# tiva_shield.net
KiCad netlist of a schematic drawn in Altium Designer
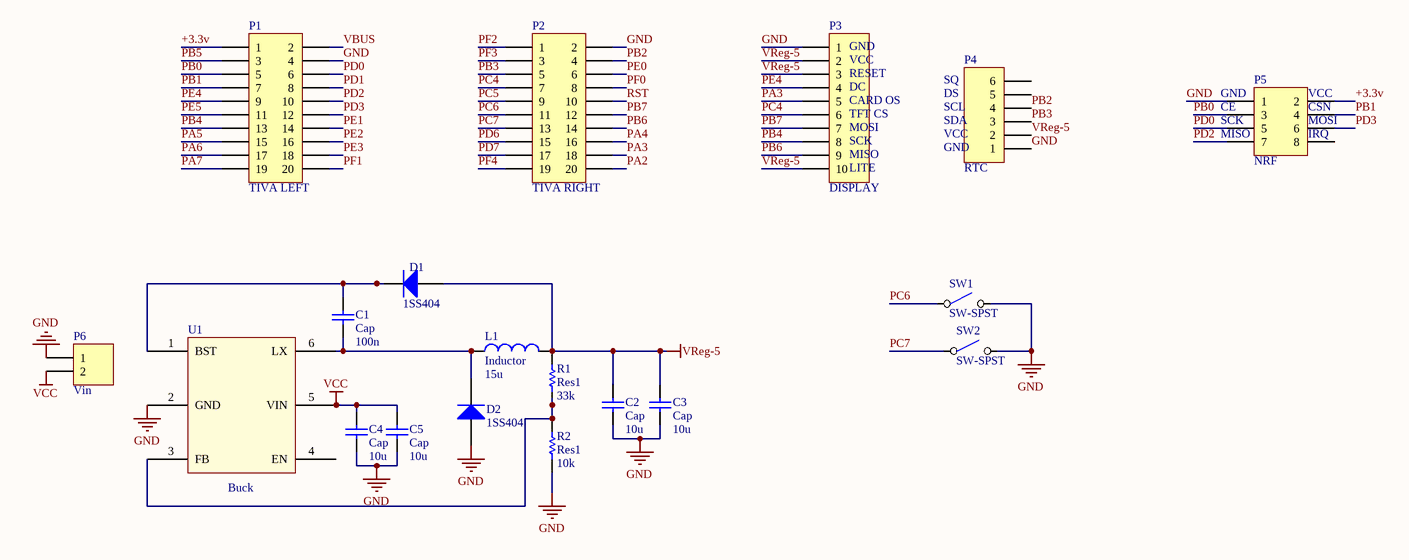
[diagram p0: tiva_shield.SchDoc]

(export (version "E")
  (design (tool "Eeschema 10.0.6"))
  (components
    (comp (ref "C1")
      (value "Cap")
      (footprint "0603E")
      (description "Capacitor")
      (fields (field (name "ALTIUM_VALUE") "100n") (field (name "PUBLISHER") "Altium Limited"))
      (libsource (lib "Miscellaneous Devices") (part "Cap"))
    )
    (comp (ref "C2")
      (value "Cap")
      (footprint "C0805")
      (description "Capacitor")
      (fields (field (name "ALTIUM_VALUE") "10u") (field (name "PUBLISHER") "Altium Limited"))
      (libsource (lib "Miscellaneous Devices") (part "Cap"))
    )
    (comp (ref "C3")
      (value "Cap")
      (footprint "C0805")
      (description "Capacitor")
      (fields (field (name "ALTIUM_VALUE") "10u") (field (name "PUBLISHER") "Altium Limited"))
      (libsource (lib "Miscellaneous Devices") (part "Cap"))
    )
    (comp (ref "C4")
      (value "Cap")
      (footprint "C0805")
      (description "Capacitor")
      (fields (field (name "ALTIUM_VALUE") "10u") (field (name "PUBLISHER") "Altium Limited"))
      (libsource (lib "Miscellaneous Devices") (part "Cap"))
    )
    (comp (ref "C5")
      (value "Cap")
      (footprint "C0805")
      (description "Capacitor")
      (fields (field (name "ALTIUM_VALUE") "10u") (field (name "PUBLISHER") "Altium Limited"))
      (libsource (lib "Miscellaneous Devices") (part "Cap"))
    )
    (comp (ref "D1")
      (value "1SS404")
      (footprint "SOD-323")
      (description "Silicon RF Switching Diode for VHF Band Switching in TV/VTR Tuners")
      (fields (field (name "PUBLISHER") "Altium Limited"))
      (libsource (lib "Infineon Discrete Diode") (part "BA592"))
    )
    (comp (ref "D2")
      (value "1SS404")
      (footprint "SOD-323")
      (description "Silicon RF Switching Diode for VHF Band Switching in TV/VTR Tuners")
      (fields (field (name "PUBLISHER") "Altium Limited"))
      (libsource (lib "Infineon Discrete Diode") (part "BA592"))
    )
    (comp (ref "L1")
      (value "Inductor")
      (footprint "5828-INDUCTOR")
      (fields (field (name "ALTIUM_VALUE") "15u") (field (name "PUBLISHER") "Altium Limited"))
      (libsource (lib "Miscellaneous Devices") (part "Inductor"))
    )
    (comp (ref "P1")
      (value "TIVA LEFT")
      (footprint "HDR2X10")
      (description "Header, 10-Pin, Dual row")
      (fields (field (name "PUBLISHER") "Altium Limited"))
      (libsource (lib "Miscellaneous Connectors") (part "Header 10X2"))
    )
    (comp (ref "P2")
      (value "TIVA RIGHT")
      (footprint "HDR2X10")
      (description "Header, 10-Pin, Dual row")
      (fields (field (name "PUBLISHER") "Altium Limited"))
      (libsource (lib "Miscellaneous Connectors") (part "Header 10X2"))
    )
    (comp (ref "P3")
      (value "DISPLAY")
      (footprint "HDR1X10")
      (description "Header, 10-Pin")
      (fields (field (name "PUBLISHER") "Altium Limited"))
      (libsource (lib "Miscellaneous Connectors") (part "Header 10"))
    )
    (comp (ref "P4")
      (value "RTC")
      (footprint "HDR1X6")
      (description "Header, 6-Pin")
      (fields (field (name "PUBLISHER") "Altium Limited"))
      (libsource (lib "Miscellaneous Connectors") (part "Header 6"))
    )
    (comp (ref "P5")
      (value "NRF")
      (footprint "HDR2X4")
      (description "Header, 4-Pin, Dual row")
      (fields (field (name "PUBLISHER") "Altium Limited"))
      (libsource (lib "Miscellaneous Connectors") (part "Header 4X2"))
    )
    (comp (ref "P6")
      (value "Vin")
      (footprint "HDR1X2")
      (description "Header, 2-Pin")
      (fields (field (name "PUBLISHER") "Altium Limited"))
      (libsource (lib "Miscellaneous Connectors") (part "Header 2"))
    )
    (comp (ref "R1")
      (value "Res1")
      (footprint "0603E")
      (description "Resistor")
      (fields (field (name "ALTIUM_VALUE") "33k") (field (name "PUBLISHER") "Altium Limited"))
      (libsource (lib "Miscellaneous Devices") (part "Res1"))
    )
    (comp (ref "R2")
      (value "Res1")
      (footprint "0603E")
      (description "Resistor")
      (fields (field (name "ALTIUM_VALUE") "10k") (field (name "PUBLISHER") "Altium Limited"))
      (libsource (lib "Miscellaneous Devices") (part "Res1"))
    )
    (comp (ref "SW1")
      (value "SW-SPST")
      (footprint "Switch - SMD")
      (libsource (lib "KBsch01") (part "SW-SPST"))
    )
    (comp (ref "SW2")
      (value "SW-SPST")
      (footprint "Switch - SMD")
      (libsource (lib "KBsch01") (part "SW-SPST"))
    )
    (comp (ref "U1") (value "Buck") (footprint "SOT23-6") (libsource (lib "aoz1280ci") (part "Component_1")))
  )
  (nets
    (net (code "1") (name "/+3.3v") (class "Default")
      (node (ref "P1") (pin "1") (pinfunction "1_1") (pintype "passive"))
      (node (ref "P5") (pin "2") (pinfunction "2_2") (pintype "passive"))
    )
    (net (code "2") (name "/PA2") (class "Default")
      (node (ref "P2") (pin "20") (pinfunction "20_20") (pintype "passive"))
    )
    (net (code "3") (name "/PA3") (class "Default")
      (node (ref "P2") (pin "18") (pinfunction "18_18") (pintype "passive"))
      (node (ref "P3") (pin "5") (pinfunction "5_5") (pintype "passive"))
    )
    (net (code "4") (name "/PA4") (class "Default")
      (node (ref "P2") (pin "16") (pinfunction "16_16") (pintype "passive"))
    )
    (net (code "5") (name "/PA5") (class "Default")
      (node (ref "P1") (pin "15") (pinfunction "15_15") (pintype "passive"))
    )
    (net (code "6") (name "/PA6") (class "Default")
      (node (ref "P1") (pin "17") (pinfunction "17_17") (pintype "passive"))
    )
    (net (code "7") (name "/PA7") (class "Default")
      (node (ref "P1") (pin "19") (pinfunction "19_19") (pintype "passive"))
    )
    (net (code "8") (name "/PB0") (class "Default")
      (node (ref "P1") (pin "5") (pinfunction "5_5") (pintype "passive"))
      (node (ref "P5") (pin "3") (pinfunction "3_3") (pintype "passive"))
    )
    (net (code "9") (name "/PB1") (class "Default")
      (node (ref "P1") (pin "7") (pinfunction "7_7") (pintype "passive"))
      (node (ref "P5") (pin "4") (pinfunction "4_4") (pintype "passive"))
    )
    (net (code "10") (name "/PB2") (class "Default")
      (node (ref "P2") (pin "4") (pinfunction "4_4") (pintype "passive"))
      (node (ref "P4") (pin "4") (pinfunction "4_4") (pintype "passive"))
    )
    (net (code "11") (name "/PB3") (class "Default")
      (node (ref "P2") (pin "5") (pinfunction "5_5") (pintype "passive"))
      (node (ref "P4") (pin "3") (pinfunction "3_3") (pintype "passive"))
    )
    (net (code "12") (name "/PB4") (class "Default")
      (node (ref "P1") (pin "13") (pinfunction "13_13") (pintype "passive"))
      (node (ref "P3") (pin "8") (pinfunction "8_8") (pintype "passive"))
    )
    (net (code "13") (name "/PB5") (class "Default")
      (node (ref "P1") (pin "3") (pinfunction "3_3") (pintype "passive"))
    )
    (net (code "14") (name "/PB6") (class "Default")
      (node (ref "P2") (pin "14") (pinfunction "14_14") (pintype "passive"))
      (node (ref "P3") (pin "9") (pinfunction "9_9") (pintype "passive"))
    )
    (net (code "15") (name "/PB7") (class "Default")
      (node (ref "P2") (pin "12") (pinfunction "12_12") (pintype "passive"))
      (node (ref "P3") (pin "7") (pinfunction "7_7") (pintype "passive"))
    )
    (net (code "16") (name "/PC4") (class "Default")
      (node (ref "P2") (pin "7") (pinfunction "7_7") (pintype "passive"))
      (node (ref "P3") (pin "6") (pinfunction "6_6") (pintype "passive"))
    )
    (net (code "17") (name "/PC5") (class "Default")
      (node (ref "P2") (pin "9") (pinfunction "9_9") (pintype "passive"))
    )
    (net (code "18") (name "/PC6") (class "Default")
      (node (ref "P2") (pin "11") (pinfunction "11_11") (pintype "passive"))
      (node (ref "SW1") (pin "1") (pintype "passive"))
    )
    (net (code "19") (name "/PC7") (class "Default")
      (node (ref "P2") (pin "13") (pinfunction "13_13") (pintype "passive"))
      (node (ref "SW2") (pin "1") (pintype "passive"))
    )
    (net (code "20") (name "/PD0") (class "Default")
      (node (ref "P1") (pin "6") (pinfunction "6_6") (pintype "passive"))
      (node (ref "P5") (pin "5") (pinfunction "5_5") (pintype "passive"))
    )
    (net (code "21") (name "/PD1") (class "Default")
      (node (ref "P1") (pin "8") (pinfunction "8_8") (pintype "passive"))
    )
    (net (code "22") (name "/PD2") (class "Default")
      (node (ref "P1") (pin "10") (pinfunction "10_10") (pintype "passive"))
      (node (ref "P5") (pin "7") (pinfunction "7_7") (pintype "passive"))
    )
    (net (code "23") (name "/PD3") (class "Default")
      (node (ref "P1") (pin "12") (pinfunction "12_12") (pintype "passive"))
      (node (ref "P5") (pin "6") (pinfunction "6_6") (pintype "passive"))
    )
    (net (code "24") (name "/PD6") (class "Default")
      (node (ref "P2") (pin "15") (pinfunction "15_15") (pintype "passive"))
    )
    (net (code "25") (name "/PD7") (class "Default")
      (node (ref "P2") (pin "17") (pinfunction "17_17") (pintype "passive"))
    )
    (net (code "26") (name "/PE0") (class "Default")
      (node (ref "P2") (pin "6") (pinfunction "6_6") (pintype "passive"))
    )
    (net (code "27") (name "/PE1") (class "Default")
      (node (ref "P1") (pin "14") (pinfunction "14_14") (pintype "passive"))
    )
    (net (code "28") (name "/PE2") (class "Default")
      (node (ref "P1") (pin "16") (pinfunction "16_16") (pintype "passive"))
    )
    (net (code "29") (name "/PE3") (class "Default")
      (node (ref "P1") (pin "18") (pinfunction "18_18") (pintype "passive"))
    )
    (net (code "30") (name "/PE4") (class "Default")
      (node (ref "P1") (pin "9") (pinfunction "9_9") (pintype "passive"))
      (node (ref "P3") (pin "4") (pinfunction "4_4") (pintype "passive"))
    )
    (net (code "31") (name "/PE5") (class "Default")
      (node (ref "P1") (pin "11") (pinfunction "11_11") (pintype "passive"))
    )
    (net (code "32") (name "/PF0") (class "Default")
      (node (ref "P2") (pin "8") (pinfunction "8_8") (pintype "passive"))
    )
    (net (code "33") (name "/PF1") (class "Default")
      (node (ref "P1") (pin "20") (pinfunction "20_20") (pintype "passive"))
    )
    (net (code "34") (name "/PF2") (class "Default")
      (node (ref "P2") (pin "1") (pinfunction "1_1") (pintype "passive"))
    )
    (net (code "35") (name "/PF3") (class "Default")
      (node (ref "P2") (pin "3") (pinfunction "3_3") (pintype "passive"))
    )
    (net (code "36") (name "/PF4") (class "Default")
      (node (ref "P2") (pin "19") (pinfunction "19_19") (pintype "passive"))
    )
    (net (code "37") (name "/RST") (class "Default")
      (node (ref "P2") (pin "10") (pinfunction "10_10") (pintype "passive"))
    )
    (net (code "38") (name "/VBUS") (class "Default")
      (node (ref "P1") (pin "2") (pinfunction "2_2") (pintype "passive"))
    )
    (net (code "39") (name "GND") (class "Default")
      (node (ref "C2") (pin "1") (pinfunction "1_1") (pintype "passive"))
      (node (ref "C3") (pin "1") (pinfunction "1_1") (pintype "passive"))
      (node (ref "C4") (pin "2") (pinfunction "2_2") (pintype "passive"))
      (node (ref "C5") (pin "2") (pinfunction "2_2") (pintype "passive"))
      (node (ref "D2") (pin "2") (pinfunction "A_2") (pintype "passive"))
      (node (ref "P1") (pin "4") (pinfunction "4_4") (pintype "passive"))
      (node (ref "P2") (pin "2") (pinfunction "2_2") (pintype "passive"))
      (node (ref "P3") (pin "1") (pinfunction "1_1") (pintype "passive"))
      (node (ref "P4") (pin "1") (pinfunction "1_1") (pintype "passive"))
      (node (ref "P5") (pin "1") (pinfunction "1_1") (pintype "passive"))
      (node (ref "P6") (pin "1") (pinfunction "1_1") (pintype "passive"))
      (node (ref "R2") (pin "1") (pinfunction "1_1") (pintype "passive"))
      (node (ref "SW1") (pin "2") (pintype "passive"))
      (node (ref "SW2") (pin "2") (pintype "passive"))
      (node (ref "U1") (pin "2") (pinfunction "GND_2") (pintype "passive"))
    )
    (net (code "40") (name "Net-(D1-K)") (class "Default")
      (node (ref "C1") (pin "1") (pinfunction "1_1") (pintype "passive"))
      (node (ref "D1") (pin "1") (pinfunction "K_1") (pintype "passive"))
      (node (ref "U1") (pin "1") (pinfunction "BST_1") (pintype "passive"))
    )
    (net (code "41") (name "Net-(D2-K)") (class "Default")
      (node (ref "C1") (pin "2") (pinfunction "2_2") (pintype "passive"))
      (node (ref "D2") (pin "1") (pinfunction "K_1") (pintype "passive"))
      (node (ref "L1") (pin "1") (pinfunction "1_1") (pintype "passive"))
      (node (ref "U1") (pin "6") (pinfunction "LX_6") (pintype "passive"))
    )
    (net (code "42") (name "Net-(U1-FB)") (class "Default")
      (node (ref "R1") (pin "1") (pinfunction "1_1") (pintype "passive"))
      (node (ref "R2") (pin "2") (pinfunction "2_2") (pintype "passive"))
      (node (ref "U1") (pin "3") (pinfunction "FB_3") (pintype "passive"))
    )
    (net (code "43") (name "VCC") (class "Default")
      (node (ref "C4") (pin "1") (pinfunction "1_1") (pintype "passive"))
      (node (ref "C5") (pin "1") (pinfunction "1_1") (pintype "passive"))
      (node (ref "P6") (pin "2") (pinfunction "2_2") (pintype "passive"))
      (node (ref "U1") (pin "5") (pinfunction "VIN_5") (pintype "passive"))
    )
    (net (code "44") (name "VReg-5") (class "Default")
      (node (ref "C2") (pin "2") (pinfunction "2_2") (pintype "passive"))
      (node (ref "C3") (pin "2") (pinfunction "2_2") (pintype "passive"))
      (node (ref "D1") (pin "2") (pinfunction "A_2") (pintype "passive"))
      (node (ref "L1") (pin "2") (pinfunction "2_2") (pintype "passive"))
      (node (ref "P3") (pin "10") (pinfunction "10_10") (pintype "passive"))
      (node (ref "P3") (pin "2") (pinfunction "2_2") (pintype "passive"))
      (node (ref "P3") (pin "3") (pinfunction "3_3") (pintype "passive"))
      (node (ref "P4") (pin "2") (pinfunction "2_2") (pintype "passive"))
      (node (ref "R1") (pin "2") (pinfunction "2_2") (pintype "passive"))
    )
    (net (code "45") (name "unconnected-(P4-Pad5)") (class "Default")
      (node (ref "P4") (pin "5") (pinfunction "5_5") (pintype "passive"))
    )
    (net (code "46") (name "unconnected-(P4-Pad6)") (class "Default")
      (node (ref "P4") (pin "6") (pinfunction "6_6") (pintype "passive"))
    )
    (net (code "47") (name "unconnected-(P5-Pad8)") (class "Default")
      (node (ref "P5") (pin "8") (pinfunction "8_8") (pintype "passive"))
    )
    (net (code "48") (name "unconnected-(U1-EN-Pad4)") (class "Default")
      (node (ref "U1") (pin "4") (pinfunction "EN_4") (pintype "passive"))
    )
  )
)
